# untitled.net
KiCad netlist of a schematic drawn in EAGLE
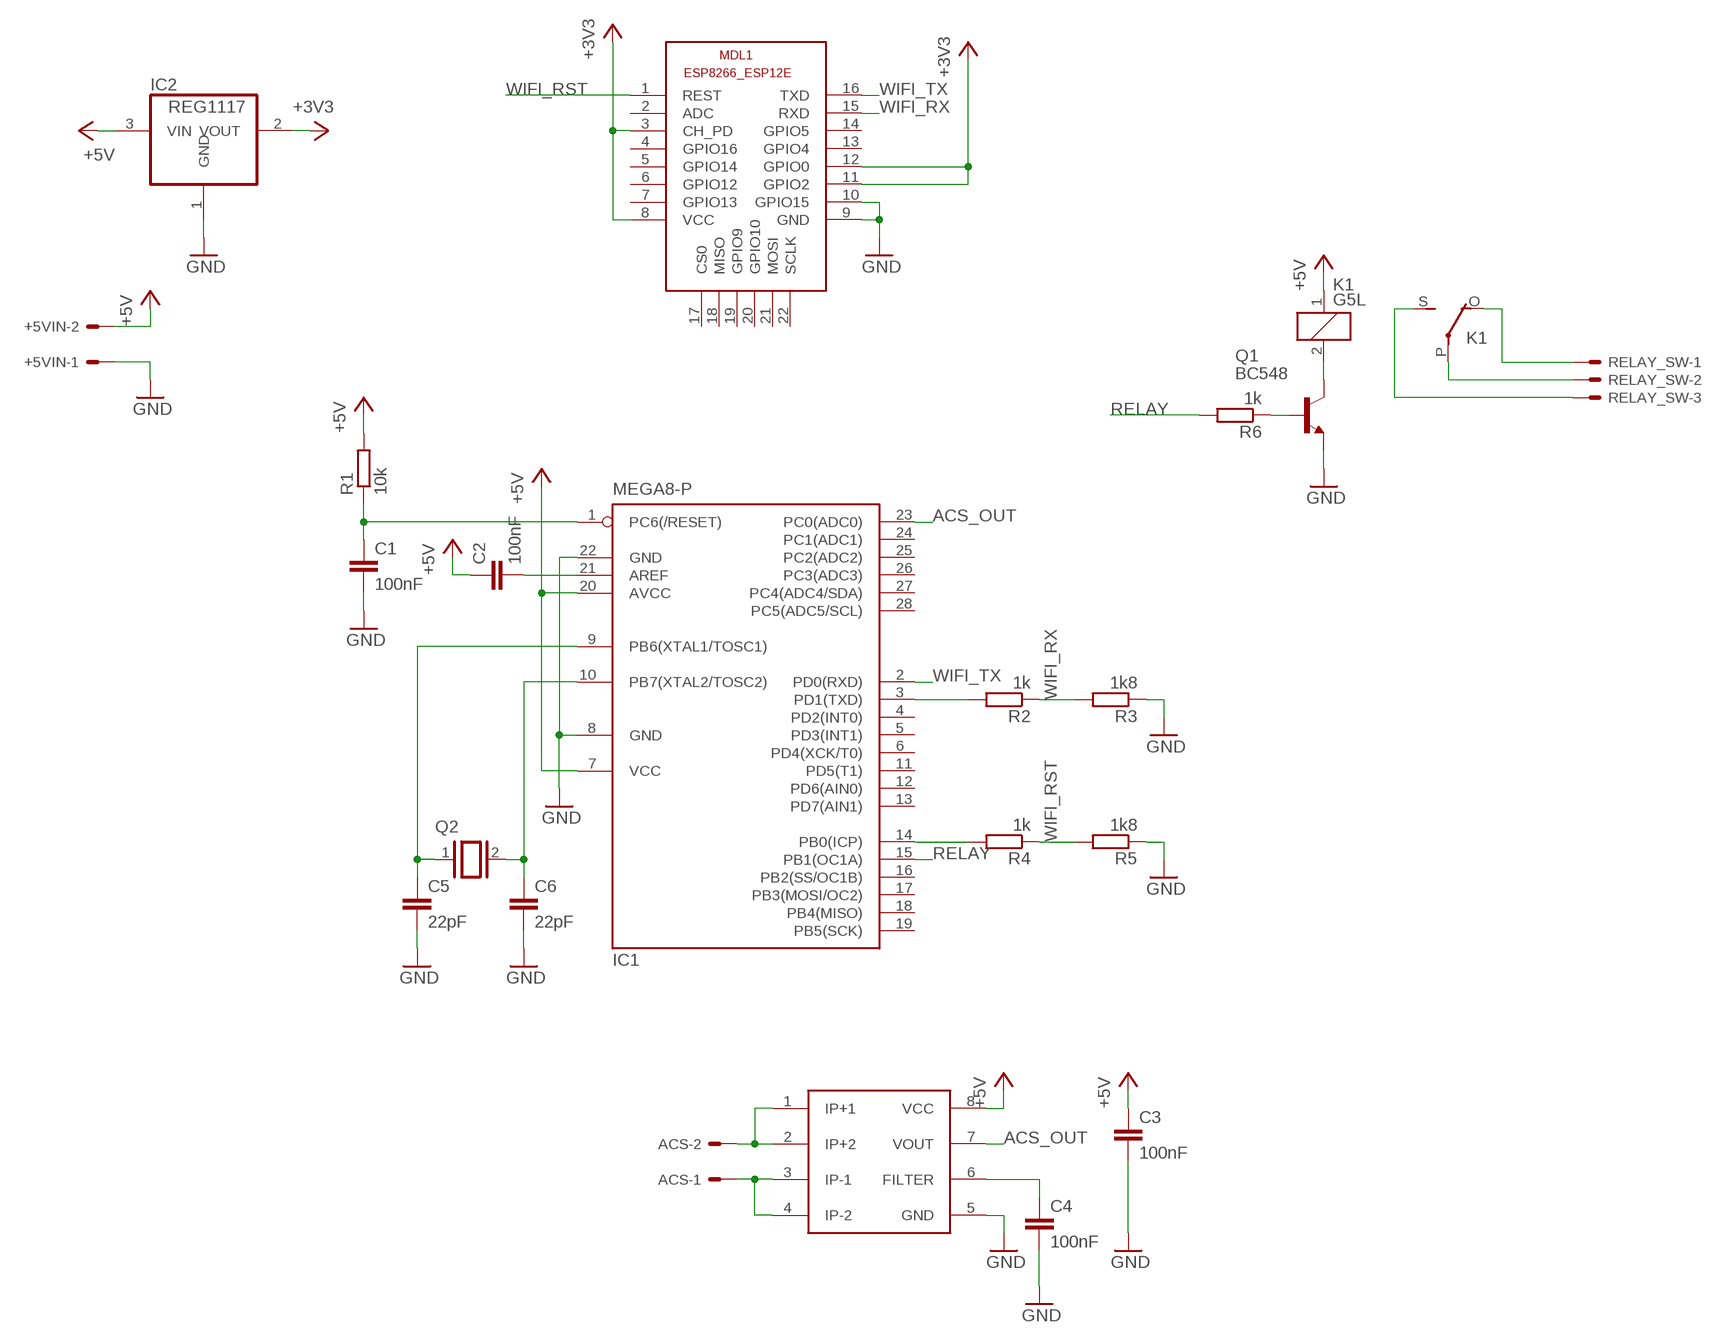
[diagram p0: schematic, sheet 1]

(export (version "E")
  (design (tool "Eeschema 10.0.6"))
  (components
    (comp (ref "+5VIN")
      (value "KK-156-2")
      (footprint "eagle-import:KK-156-2")
      (libsource (lib "eagle-import") (part "KK-156-2"))
    )
    (comp (ref "ACS")
      (value "KK-156-2")
      (footprint "eagle-import:KK-156-2")
      (libsource (lib "eagle-import") (part "KK-156-2"))
    )
    (comp (ref "C1")
      (value "100nF")
      (footprint "eagle-import:C050-030X075")
      (libsource (lib "eagle-import") (part "C-EU050-030X075"))
    )
    (comp (ref "C2")
      (value "100nF")
      (footprint "eagle-import:C050-030X075")
      (libsource (lib "eagle-import") (part "C-EU050-030X075"))
    )
    (comp (ref "C3")
      (value "100nF")
      (footprint "eagle-import:C050-030X075")
      (libsource (lib "eagle-import") (part "C-EU050-030X075"))
    )
    (comp (ref "C4")
      (value "100nF")
      (footprint "eagle-import:C050-030X075")
      (libsource (lib "eagle-import") (part "C-EU050-030X075"))
    )
    (comp (ref "C5")
      (value "22pF")
      (footprint "eagle-import:C050-030X075")
      (libsource (lib "eagle-import") (part "C-EU050-030X075"))
    )
    (comp (ref "C6")
      (value "22pF")
      (footprint "eagle-import:C050-030X075")
      (libsource (lib "eagle-import") (part "C-EU050-030X075"))
    )
    (comp (ref "IC1")
      (value "MEGA8-P")
      (footprint "eagle-import:DIL28-3")
      (libsource (lib "eagle-import") (part "MEGA8-P"))
    )
    (comp (ref "IC2")
      (value "REG1117")
      (footprint "eagle-import:SOT223")
      (libsource (lib "eagle-import") (part "REG1117"))
    )
    (comp (ref "K1")
      (value "G5L")
      (footprint "eagle-import:G5LE")
      (libsource (lib "eagle-import") (part "G5L"))
    )
    (comp (ref "MDL1")
      (value "ESP8266-12EESP8266-ESP12E")
      (footprint "eagle-import:ESP8266-ESP12E")
      (libsource (lib "eagle-import") (part "ESP8266-12EESP8266-ESP12E"))
    )
    (comp (ref "Q1")
      (value "BC548")
      (footprint "eagle-import:TO92-EBC")
      (libsource (lib "eagle-import") (part "BC548"))
    )
    (comp (ref "Q2")
      (value "XTAL/S")
      (footprint "eagle-import:QS")
      (libsource (lib "eagle-import") (part "XTAL/S"))
    )
    (comp (ref "R1")
      (value "10k")
      (footprint "eagle-import:0204_5")
      (libsource (lib "eagle-import") (part "R-EU_0204/5"))
    )
    (comp (ref "R2")
      (value "1k")
      (footprint "eagle-import:0204_5")
      (libsource (lib "eagle-import") (part "R-EU_0204/5"))
    )
    (comp (ref "R3")
      (value "1k8")
      (footprint "eagle-import:0204_5")
      (libsource (lib "eagle-import") (part "R-EU_0204/5"))
    )
    (comp (ref "R4")
      (value "1k")
      (footprint "eagle-import:0204_5")
      (libsource (lib "eagle-import") (part "R-EU_0204/5"))
    )
    (comp (ref "R5")
      (value "1k8")
      (footprint "eagle-import:0204_5")
      (libsource (lib "eagle-import") (part "R-EU_0204/5"))
    )
    (comp (ref "R6")
      (value "1k")
      (footprint "eagle-import:0204_5")
      (libsource (lib "eagle-import") (part "R-EU_0204/5"))
    )
    (comp (ref "RELAY_SW")
      (value "KK-156-3")
      (footprint "eagle-import:KK-156-3")
      (libsource (lib "eagle-import") (part "KK-156-3"))
    )
    (comp (ref "U$1")
      (value "ACS712")
      (footprint "eagle-import:SO08")
      (libsource (lib "eagle-import") (part "ACS712"))
    )
  )
  (nets
    (net (code "1") (name "+3V3") (class "Default")
      (node (ref "IC2") (pin "2") (pinfunction "VOUT_2") (pintype "output"))
      (node (ref "MDL1") (pin "11") (pinfunction "GPIO2_11") (pintype "bidirectional"))
      (node (ref "MDL1") (pin "12") (pinfunction "GPIO0_12") (pintype "bidirectional"))
      (node (ref "MDL1") (pin "3") (pinfunction "CH_PD_3") (pintype "bidirectional"))
      (node (ref "MDL1") (pin "8") (pinfunction "VCC_8") (pintype "bidirectional"))
    )
    (net (code "2") (name "+5V") (class "Default")
      (node (ref "+5VIN") (pin "2") (pinfunction "S_2") (pintype "passive"))
      (node (ref "C2") (pin "1") (pinfunction "1_1") (pintype "passive"))
      (node (ref "C3") (pin "1") (pinfunction "1_1") (pintype "passive"))
      (node (ref "IC1") (pin "20") (pinfunction "AVCC_20") (pintype "power_in"))
      (node (ref "IC1") (pin "7") (pinfunction "VCC_7") (pintype "power_in"))
      (node (ref "IC2") (pin "3") (pinfunction "VIN_3") (pintype "input"))
      (node (ref "K1") (pin "1") (pinfunction "1_1") (pintype "passive"))
      (node (ref "R1") (pin "2") (pinfunction "2_2") (pintype "passive"))
      (node (ref "U$1") (pin "8") (pinfunction "VCC_8") (pintype "bidirectional"))
    )
    (net (code "3") (name "/ACS_OUT") (class "Default")
      (node (ref "IC1") (pin "23") (pinfunction "PC0(ADC0)_23") (pintype "bidirectional"))
      (node (ref "U$1") (pin "7") (pinfunction "VOUT_7") (pintype "bidirectional"))
    )
    (net (code "4") (name "/RELAY") (class "Default")
      (node (ref "IC1") (pin "15") (pinfunction "PB1(OC1A)_15") (pintype "bidirectional"))
      (node (ref "R6") (pin "2") (pinfunction "2_2") (pintype "passive"))
    )
    (net (code "5") (name "/WIFI_RST") (class "Default")
      (node (ref "MDL1") (pin "1") (pinfunction "REST_1") (pintype "bidirectional"))
      (node (ref "R4") (pin "1") (pinfunction "1_1") (pintype "passive"))
      (node (ref "R5") (pin "2") (pinfunction "2_2") (pintype "passive"))
    )
    (net (code "6") (name "/WIFI_RX") (class "Default")
      (node (ref "MDL1") (pin "15") (pinfunction "RXD_15") (pintype "bidirectional"))
      (node (ref "R2") (pin "1") (pinfunction "1_1") (pintype "passive"))
      (node (ref "R3") (pin "2") (pinfunction "2_2") (pintype "passive"))
    )
    (net (code "7") (name "/WIFI_TX") (class "Default")
      (node (ref "IC1") (pin "2") (pinfunction "PD0(RXD)_2") (pintype "bidirectional"))
      (node (ref "MDL1") (pin "16") (pinfunction "TXD_16") (pintype "bidirectional"))
    )
    (net (code "8") (name "GND") (class "Default")
      (node (ref "+5VIN") (pin "1") (pinfunction "S_1") (pintype "passive"))
      (node (ref "C1") (pin "2") (pinfunction "2_2") (pintype "passive"))
      (node (ref "C3") (pin "2") (pinfunction "2_2") (pintype "passive"))
      (node (ref "C4") (pin "2") (pinfunction "2_2") (pintype "passive"))
      (node (ref "C5") (pin "2") (pinfunction "2_2") (pintype "passive"))
      (node (ref "C6") (pin "2") (pinfunction "2_2") (pintype "passive"))
      (node (ref "IC1") (pin "22") (pinfunction "GND_22") (pintype "power_in"))
      (node (ref "IC1") (pin "8") (pinfunction "GND_8") (pintype "power_in"))
      (node (ref "IC2") (pin "1") (pinfunction "GND_1") (pintype "power_in"))
      (node (ref "MDL1") (pin "10") (pinfunction "GPIO15_10") (pintype "bidirectional"))
      (node (ref "MDL1") (pin "9") (pinfunction "GND_9") (pintype "bidirectional"))
      (node (ref "Q1") (pin "E") (pinfunction "E_E") (pintype "passive"))
      (node (ref "R3") (pin "1") (pinfunction "1_1") (pintype "passive"))
      (node (ref "R5") (pin "1") (pinfunction "1_1") (pintype "passive"))
      (node (ref "U$1") (pin "5") (pinfunction "GND_5") (pintype "bidirectional"))
    )
    (net (code "9") (name "Net-(ACSA-S)") (class "Default")
      (node (ref "ACS") (pin "1") (pinfunction "S_1") (pintype "passive"))
      (node (ref "U$1") (pin "3") (pinfunction "IP-1_3") (pintype "bidirectional"))
      (node (ref "U$1") (pin "4") (pinfunction "IP-2_4") (pintype "bidirectional"))
    )
    (net (code "10") (name "Net-(ACSB-S)") (class "Default")
      (node (ref "ACS") (pin "2") (pinfunction "S_2") (pintype "passive"))
      (node (ref "U$1") (pin "1") (pinfunction "IP+1_1") (pintype "bidirectional"))
      (node (ref "U$1") (pin "2") (pinfunction "IP+2_2") (pintype "bidirectional"))
    )
    (net (code "11") (name "Net-(IC1-AREF)") (class "Default")
      (node (ref "C2") (pin "2") (pinfunction "2_2") (pintype "passive"))
      (node (ref "IC1") (pin "21") (pinfunction "AREF_21") (pintype "passive"))
    )
    (net (code "12") (name "Net-(IC1-PB0(ICP))") (class "Default")
      (node (ref "IC1") (pin "14") (pinfunction "PB0(ICP)_14") (pintype "bidirectional"))
      (node (ref "R4") (pin "2") (pinfunction "2_2") (pintype "passive"))
    )
    (net (code "13") (name "Net-(IC1-PB6(XTAL1{slash}TOSC1))") (class "Default")
      (node (ref "C5") (pin "1") (pinfunction "1_1") (pintype "passive"))
      (node (ref "IC1") (pin "9") (pinfunction "PB6(XTAL1/TOSC1)_9") (pintype "bidirectional"))
      (node (ref "Q2") (pin "1") (pinfunction "1_1") (pintype "passive"))
    )
    (net (code "14") (name "Net-(IC1-PB7(XTAL2{slash}TOSC2))") (class "Default")
      (node (ref "C6") (pin "1") (pinfunction "1_1") (pintype "passive"))
      (node (ref "IC1") (pin "10") (pinfunction "PB7(XTAL2/TOSC2)_10") (pintype "bidirectional"))
      (node (ref "Q2") (pin "2") (pinfunction "2_2") (pintype "passive"))
    )
    (net (code "15") (name "Net-(IC1-PC6({slash}RESET))") (class "Default")
      (node (ref "C1") (pin "1") (pinfunction "1_1") (pintype "passive"))
      (node (ref "IC1") (pin "1") (pinfunction "PC6(/RESET)_1") (pintype "bidirectional"))
      (node (ref "R1") (pin "1") (pinfunction "1_1") (pintype "passive"))
    )
    (net (code "16") (name "Net-(IC1-PD1(TXD))") (class "Default")
      (node (ref "IC1") (pin "3") (pinfunction "PD1(TXD)_3") (pintype "bidirectional"))
      (node (ref "R2") (pin "2") (pinfunction "2_2") (pintype "passive"))
    )
    (net (code "17") (name "Net-(K1-Pad2)") (class "Default")
      (node (ref "K1") (pin "2") (pinfunction "2_2") (pintype "passive"))
      (node (ref "Q1") (pin "C") (pinfunction "C_C") (pintype "passive"))
    )
    (net (code "18") (name "Net-(Q1-PadB)") (class "Default")
      (node (ref "Q1") (pin "B") (pinfunction "B_B") (pintype "passive"))
      (node (ref "R6") (pin "1") (pinfunction "1_1") (pintype "passive"))
    )
    (net (code "19") (name "Net-(RELAY_SWA-S)") (class "Default")
      (node (ref "K1") (pin "O") (pinfunction "O_O") (pintype "passive"))
      (node (ref "RELAY_SW") (pin "1") (pinfunction "S_1") (pintype "passive"))
    )
    (net (code "20") (name "Net-(RELAY_SWB-S)") (class "Default")
      (node (ref "K1") (pin "P") (pinfunction "P_P") (pintype "passive"))
      (node (ref "RELAY_SW") (pin "2") (pinfunction "S_2") (pintype "passive"))
    )
    (net (code "21") (name "Net-(RELAY_SWC-S)") (class "Default")
      (node (ref "K1") (pin "S") (pinfunction "S_S") (pintype "passive"))
      (node (ref "RELAY_SW") (pin "3") (pinfunction "S_3") (pintype "passive"))
    )
    (net (code "22") (name "Net-(U$1-FILTER)") (class "Default")
      (node (ref "C4") (pin "1") (pinfunction "1_1") (pintype "passive"))
      (node (ref "U$1") (pin "6") (pinfunction "FILTER_6") (pintype "bidirectional"))
    )
    (net (code "23") (name "unconnected-(IC1-PB2(SS{slash}OC1B)-Pad16)") (class "Default")
      (node (ref "IC1") (pin "16") (pinfunction "PB2(SS/OC1B)_16") (pintype "bidirectional"))
    )
    (net (code "24") (name "unconnected-(IC1-PB3(MOSI{slash}OC2)-Pad17)") (class "Default")
      (node (ref "IC1") (pin "17") (pinfunction "PB3(MOSI/OC2)_17") (pintype "bidirectional"))
    )
    (net (code "25") (name "unconnected-(IC1-PB4(MISO)-Pad18)") (class "Default")
      (node (ref "IC1") (pin "18") (pinfunction "PB4(MISO)_18") (pintype "bidirectional"))
    )
    (net (code "26") (name "unconnected-(IC1-PB5(SCK)-Pad19)") (class "Default")
      (node (ref "IC1") (pin "19") (pinfunction "PB5(SCK)_19") (pintype "bidirectional"))
    )
    (net (code "27") (name "unconnected-(IC1-PC1(ADC1)-Pad24)") (class "Default")
      (node (ref "IC1") (pin "24") (pinfunction "PC1(ADC1)_24") (pintype "bidirectional"))
    )
    (net (code "28") (name "unconnected-(IC1-PC2(ADC2)-Pad25)") (class "Default")
      (node (ref "IC1") (pin "25") (pinfunction "PC2(ADC2)_25") (pintype "bidirectional"))
    )
    (net (code "29") (name "unconnected-(IC1-PC3(ADC3)-Pad26)") (class "Default")
      (node (ref "IC1") (pin "26") (pinfunction "PC3(ADC3)_26") (pintype "bidirectional"))
    )
    (net (code "30") (name "unconnected-(IC1-PC4(ADC4{slash}SDA)-Pad27)") (class "Default")
      (node (ref "IC1") (pin "27") (pinfunction "PC4(ADC4/SDA)_27") (pintype "bidirectional"))
    )
    (net (code "31") (name "unconnected-(IC1-PC5(ADC5{slash}SCL)-Pad28)") (class "Default")
      (node (ref "IC1") (pin "28") (pinfunction "PC5(ADC5/SCL)_28") (pintype "bidirectional"))
    )
    (net (code "32") (name "unconnected-(IC1-PD2(INT0)-Pad4)") (class "Default")
      (node (ref "IC1") (pin "4") (pinfunction "PD2(INT0)_4") (pintype "bidirectional"))
    )
    (net (code "33") (name "unconnected-(IC1-PD3(INT1)-Pad5)") (class "Default")
      (node (ref "IC1") (pin "5") (pinfunction "PD3(INT1)_5") (pintype "bidirectional"))
    )
    (net (code "34") (name "unconnected-(IC1-PD4(XCK{slash}T0)-Pad6)") (class "Default")
      (node (ref "IC1") (pin "6") (pinfunction "PD4(XCK/T0)_6") (pintype "bidirectional"))
    )
    (net (code "35") (name "unconnected-(IC1-PD5(T1)-Pad11)") (class "Default")
      (node (ref "IC1") (pin "11") (pinfunction "PD5(T1)_11") (pintype "bidirectional"))
    )
    (net (code "36") (name "unconnected-(IC1-PD6(AIN0)-Pad12)") (class "Default")
      (node (ref "IC1") (pin "12") (pinfunction "PD6(AIN0)_12") (pintype "bidirectional"))
    )
    (net (code "37") (name "unconnected-(IC1-PD7(AIN1)-Pad13)") (class "Default")
      (node (ref "IC1") (pin "13") (pinfunction "PD7(AIN1)_13") (pintype "bidirectional"))
    )
    (net (code "38") (name "unconnected-(MDL1-ADC-Pad2)") (class "Default")
      (node (ref "MDL1") (pin "2") (pinfunction "ADC_2") (pintype "bidirectional"))
    )
    (net (code "39") (name "unconnected-(MDL1-CS0-Pad17)") (class "Default")
      (node (ref "MDL1") (pin "17") (pinfunction "CS0_17") (pintype "bidirectional"))
    )
    (net (code "40") (name "unconnected-(MDL1-GPIO4-Pad13)") (class "Default")
      (node (ref "MDL1") (pin "13") (pinfunction "GPIO4_13") (pintype "bidirectional"))
    )
    (net (code "41") (name "unconnected-(MDL1-GPIO5-Pad14)") (class "Default")
      (node (ref "MDL1") (pin "14") (pinfunction "GPIO5_14") (pintype "bidirectional"))
    )
    (net (code "42") (name "unconnected-(MDL1-GPIO9-Pad19)") (class "Default")
      (node (ref "MDL1") (pin "19") (pinfunction "GPIO9_19") (pintype "bidirectional"))
    )
    (net (code "43") (name "unconnected-(MDL1-GPIO10-Pad20)") (class "Default")
      (node (ref "MDL1") (pin "20") (pinfunction "GPIO10_20") (pintype "bidirectional"))
    )
    (net (code "44") (name "unconnected-(MDL1-GPIO12-Pad6)") (class "Default")
      (node (ref "MDL1") (pin "6") (pinfunction "GPIO12_6") (pintype "bidirectional"))
    )
    (net (code "45") (name "unconnected-(MDL1-GPIO13-Pad7)") (class "Default")
      (node (ref "MDL1") (pin "7") (pinfunction "GPIO13_7") (pintype "bidirectional"))
    )
    (net (code "46") (name "unconnected-(MDL1-GPIO14-Pad5)") (class "Default")
      (node (ref "MDL1") (pin "5") (pinfunction "GPIO14_5") (pintype "bidirectional"))
    )
    (net (code "47") (name "unconnected-(MDL1-GPIO16-Pad4)") (class "Default")
      (node (ref "MDL1") (pin "4") (pinfunction "GPIO16_4") (pintype "bidirectional"))
    )
    (net (code "48") (name "unconnected-(MDL1-MISO-Pad18)") (class "Default")
      (node (ref "MDL1") (pin "18") (pinfunction "MISO_18") (pintype "bidirectional"))
    )
    (net (code "49") (name "unconnected-(MDL1-MOSI-Pad21)") (class "Default")
      (node (ref "MDL1") (pin "21") (pinfunction "MOSI_21") (pintype "bidirectional"))
    )
    (net (code "50") (name "unconnected-(MDL1-SCLK-Pad22)") (class "Default")
      (node (ref "MDL1") (pin "22") (pinfunction "SCLK_22") (pintype "bidirectional"))
    )
  )
)
